# Sheet1.net
KiCad netlist of a schematic drawn in Altium Designer
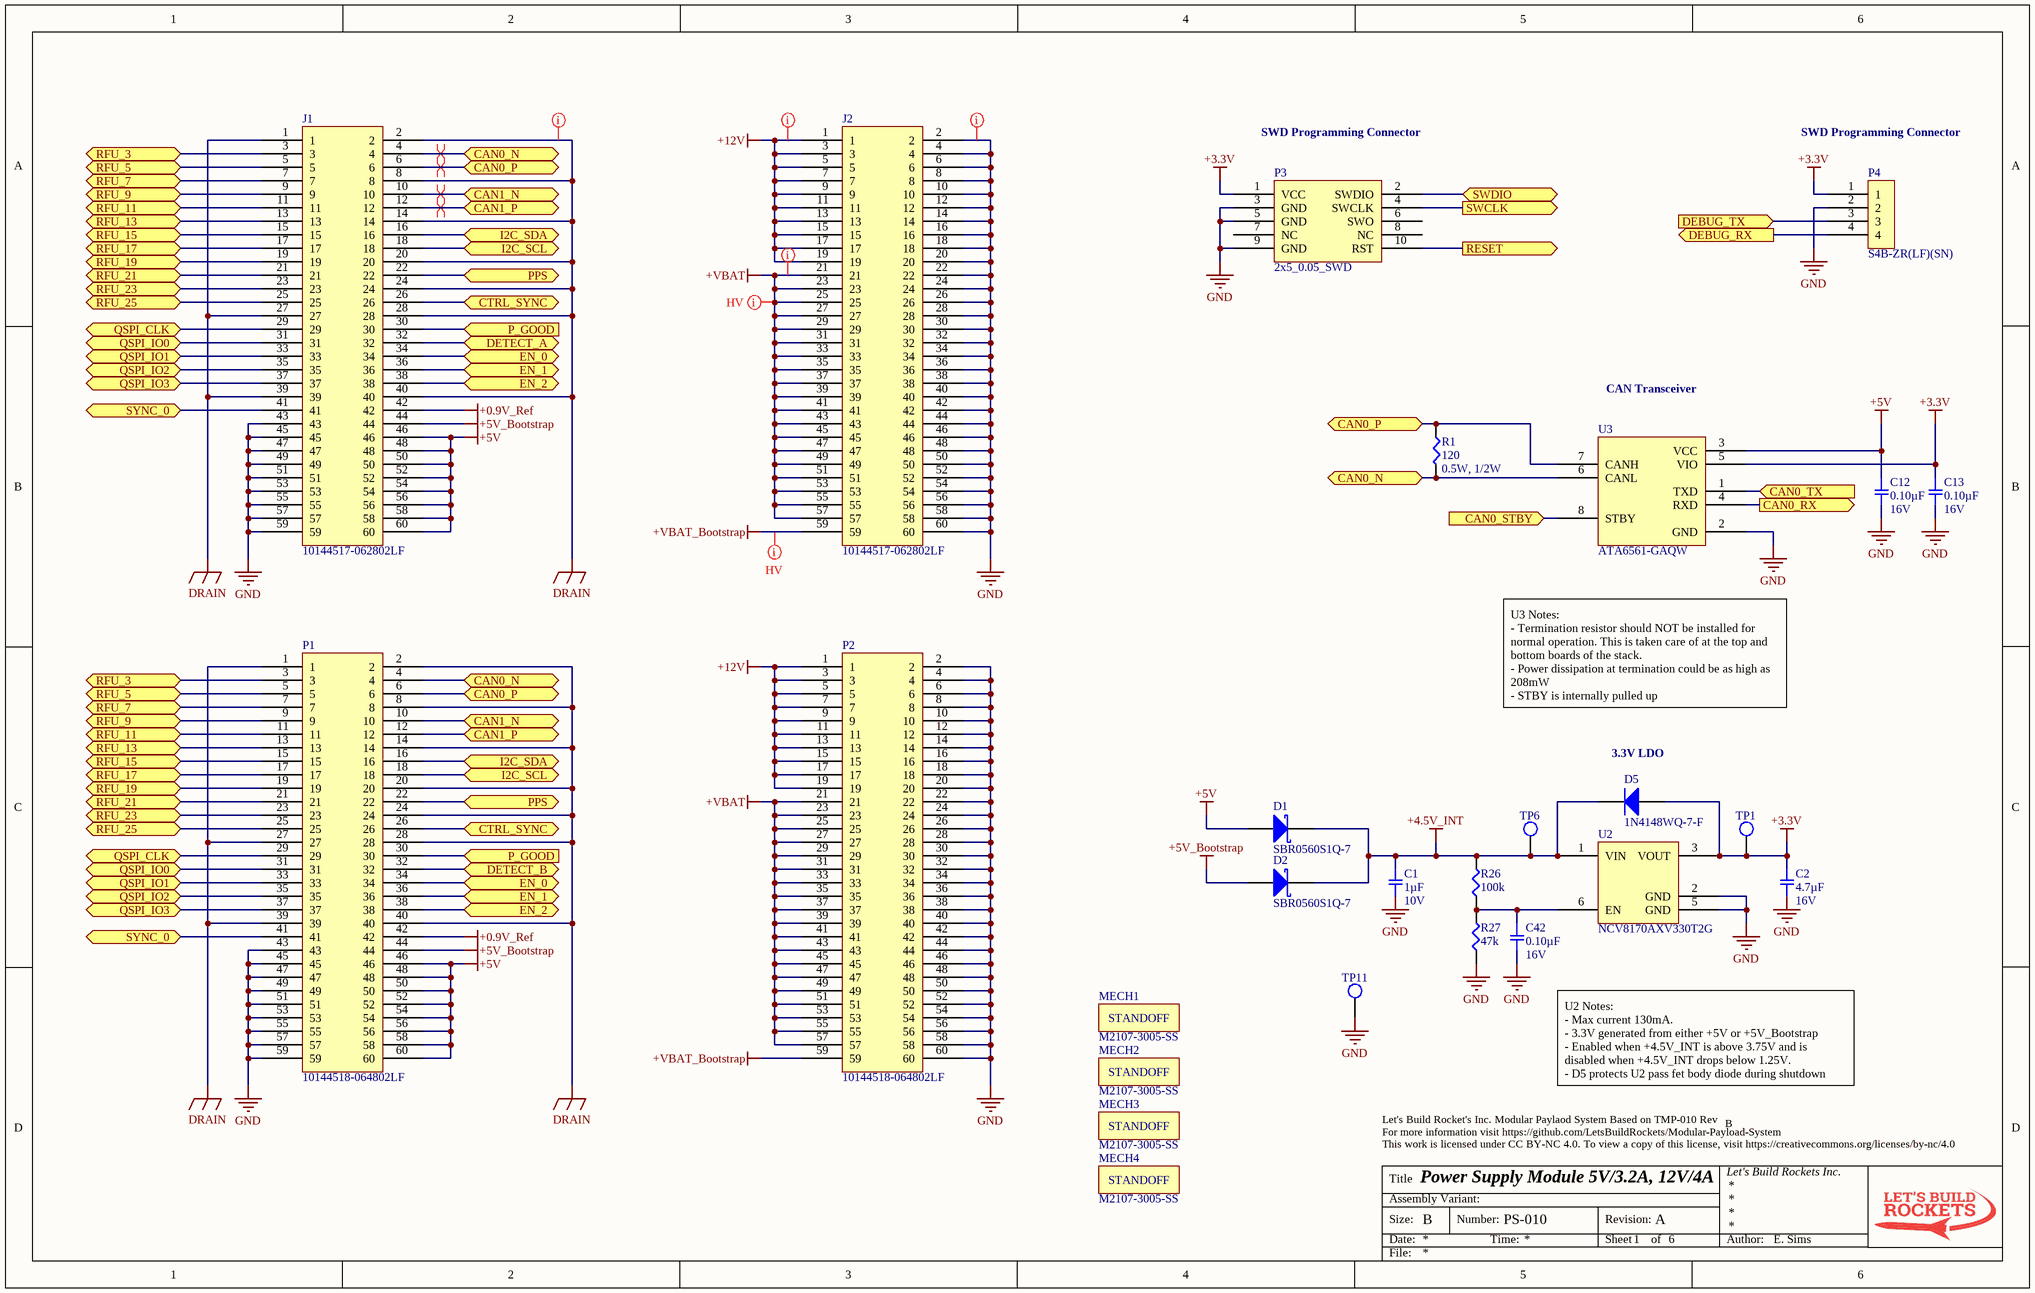
[diagram p0: Sheet1.SchDoc]

(export (version "E")
  (design (tool "Eeschema 10.0.6"))
  (components
    (comp (ref "C1")
      (value "1µF")
      (footprint "SMD-0402C")
      (description "CAP CER 1UF 10V X7S 0402")
      (fields
        (field (name "DIGI-KEY PART NUMBER") "490-13409-1-ND")
        (field (name "PART NUMBER") "GCM155C71A105KE38D")
        (field (name "VOLTAGE") "10V")
      )
      (libsource (lib "capacitor_murata_0402") (part "GCM155C71A105KE38D"))
    )
    (comp (ref "C2")
      (value "4.7µF")
      (footprint "SMD-0805C")
      (description "CAP CER 4.7UF 16V X7R 0805")
      (fields
        (field (name "DIGI-KEY PART NUMBER") "490-10557-1-ND")
        (field (name "PART NUMBER") "GCJ21BR71C475KA01L")
        (field (name "VOLTAGE") "16V")
      )
      (libsource (lib "capacitor_murata_0805") (part "GCJ21BR71C475KA01L"))
    )
    (comp (ref "C12")
      (value "0.10µF")
      (footprint "SMD-0402C")
      (description "CAP CER 0.1UF 16V X7R 0402")
      (fields
        (field (name "DIGI-KEY PART NUMBER") "490-4759-1-ND")
        (field (name "PART NUMBER") "GCM155R71C104KA55D")
        (field (name "VOLTAGE") "16V")
      )
      (libsource (lib "capacitor_murata_0402") (part "GCM155R71C104KA55D"))
    )
    (comp (ref "C13")
      (value "0.10µF")
      (footprint "SMD-0402C")
      (description "CAP CER 0.1UF 16V X7R 0402")
      (fields
        (field (name "DIGI-KEY PART NUMBER") "490-4759-1-ND")
        (field (name "PART NUMBER") "GCM155R71C104KA55D")
        (field (name "VOLTAGE") "16V")
      )
      (libsource (lib "capacitor_murata_0402") (part "GCM155R71C104KA55D"))
    )
    (comp (ref "C42")
      (value "0.10µF")
      (footprint "SMD-0402C")
      (description "CAP CER 0.1UF 16V X7R 0402")
      (fields
        (field (name "DIGI-KEY PART NUMBER") "490-4759-1-ND")
        (field (name "PART NUMBER") "GCM155R71C104KA55D")
        (field (name "VOLTAGE") "16V")
      )
      (libsource (lib "capacitor_murata_0402") (part "GCM155R71C104KA55D"))
    )
    (comp (ref "D1")
      (value "SBR0560S1Q-7")
      (footprint "SOD123")
      (libsource (lib "ModularPayload") (part "SBR0560S1Q-7"))
    )
    (comp (ref "D2")
      (value "SBR0560S1Q-7")
      (footprint "SOD123")
      (libsource (lib "ModularPayload") (part "SBR0560S1Q-7"))
    )
    (comp (ref "D5")
      (value "1N4148WQ-7-F")
      (footprint "SOD123")
      (libsource (lib "ModularPayload") (part "1N4148WQ-7-F"))
    )
    (comp (ref "J1")
      (value "10144517-062802LF")
      (footprint "10144517-062802LF")
      (libsource (lib "ModularPayload") (part "10144517-062802LF"))
    )
    (comp (ref "J2")
      (value "10144517-062802LF")
      (footprint "10144517-062802LF")
      (libsource (lib "ModularPayload") (part "10144517-062802LF"))
    )
    (comp (ref "MECH1")
      (value "M2107-3005-SS")
      (footprint "M2107-3005-SS")
      (libsource (lib "ModularPayload") (part "M2107-3005-SS"))
    )
    (comp (ref "MECH2")
      (value "M2107-3005-SS")
      (footprint "M2107-3005-SS")
      (libsource (lib "ModularPayload") (part "M2107-3005-SS"))
    )
    (comp (ref "MECH3")
      (value "M2107-3005-SS")
      (footprint "M2107-3005-SS")
      (libsource (lib "ModularPayload") (part "M2107-3005-SS"))
    )
    (comp (ref "MECH4")
      (value "M2107-3005-SS")
      (footprint "M2107-3005-SS")
      (libsource (lib "ModularPayload") (part "M2107-3005-SS"))
    )
    (comp (ref "P1")
      (value "10144518-064802LF")
      (footprint "10144518-064802LF")
      (libsource (lib "ModularPayload") (part "10144518-064802LF"))
    )
    (comp (ref "P2")
      (value "10144518-064802LF")
      (footprint "10144518-064802LF")
      (libsource (lib "ModularPayload") (part "10144518-064802LF"))
    )
    (comp (ref "P3")
      (value "2x5_0.05_SWD")
      (footprint "2x5_0.05_R")
      (libsource (lib "ModularPayload") (part "2x5_0.05_SWD"))
    )
    (comp (ref "P4")
      (value "S4B-ZR(LF)(SN)")
      (footprint "S4B-ZR(LF)(SN)")
      (libsource (lib "ModularPayload") (part "S4B-ZR(LF)(SN)"))
    )
    (comp (ref "R1")
      (value "120")
      (footprint "SMD-0805-RES")
      (description "RES SMD 120 OHM 5% 1/2W 0805")
      (fields
        (field (name "PART NUMBER") "ERJ-P6WJ121V")
        (field (name "DIGI-KEY PART NUMBER") "P16943CT-ND")
        (field (name "POWER (WATTS)") "0.5W, 1/2W")
      )
      (libsource (lib "Panasonic_ERJ_0805") (part "ERJ-P6WJ121V"))
    )
    (comp (ref "R26")
      (value "100k")
      (footprint "SMD-0402-RES")
      (description "RES SMD 100K OHM 5% 1/10W 0402")
      (fields (field (name "PART NUMBER") "ERJ-2GEJ104X") (field (name "DIGI-KEY PART NUMBER") "P100KJCT-ND"))
      (libsource (lib "Panasonic_ERJ_0402") (part "ERJ-2GEJ104X"))
    )
    (comp (ref "R27")
      (value "47k")
      (footprint "SMD-0402-RES")
      (description "RES SMD 47K OHM 5% 1/10W 0402")
      (fields (field (name "PART NUMBER") "ERJ-2GEJ473X") (field (name "DIGI-KEY PART NUMBER") "P47KJCT-ND"))
      (libsource (lib "Panasonic_ERJ_0402") (part "ERJ-2GEJ473X"))
    )
    (comp (ref "TP1") (value "TP") (footprint "TP_SMD_40") (libsource (lib "TP") (part "TP")))
    (comp (ref "TP6") (value "TP") (footprint "TP_SMD_40") (libsource (lib "TP") (part "TP")))
    (comp (ref "TP11") (value "TP") (footprint "TP_SMD_40") (libsource (lib "TP") (part "TP")))
    (comp (ref "U2")
      (value "NCV8170AXV330T2G")
      (footprint "SOTFL50P160X60-6N")
      (libsource (lib "ModularPayload") (part "NCV8170AXV330T2G"))
    )
    (comp (ref "U3")
      (value "ATA6561-GAQW")
      (footprint "SOIC127P600X175-8N")
      (libsource (lib "ModularPayload") (part "ATA6561-GAQW"))
    )
  )
  (nets
    (net (code "1") (name "+0.9V_Ref") (class "Default")
      (node (ref "J1") (pin "42") (pinfunction "42_42") (pintype "passive"))
      (node (ref "P1") (pin "42") (pinfunction "42_42") (pintype "passive"))
    )
    (net (code "2") (name "+3.3V") (class "Default")
      (node (ref "C13") (pin "1") (pinfunction "1_1") (pintype "passive"))
      (node (ref "C2") (pin "2") (pinfunction "2_2") (pintype "passive"))
      (node (ref "D5") (pin "A") (pinfunction "A_A") (pintype "passive"))
      (node (ref "P3") (pin "1") (pinfunction "VCC_1") (pintype "passive"))
      (node (ref "P4") (pin "1") (pinfunction "1_1") (pintype "passive"))
      (node (ref "TP1") (pin "1") (pintype "passive"))
      (node (ref "U2") (pin "3") (pinfunction "VOUT_3") (pintype "passive"))
      (node (ref "U3") (pin "5") (pinfunction "VIO_5") (pintype "passive"))
    )
    (net (code "3") (name "+4.5V_INT") (class "Default")
      (node (ref "C1") (pin "2") (pinfunction "2_2") (pintype "passive"))
      (node (ref "D1") (pin "K") (pinfunction "K_K") (pintype "passive"))
      (node (ref "D2") (pin "K") (pinfunction "K_K") (pintype "passive"))
      (node (ref "D5") (pin "K") (pinfunction "K_K") (pintype "passive"))
      (node (ref "R26") (pin "2") (pinfunction "2_2") (pintype "passive"))
      (node (ref "TP6") (pin "1") (pintype "passive"))
      (node (ref "U2") (pin "1") (pinfunction "VIN_1") (pintype "passive"))
    )
    (net (code "4") (name "+5V") (class "Default")
      (node (ref "C12") (pin "1") (pinfunction "1_1") (pintype "passive"))
      (node (ref "D1") (pin "A") (pinfunction "A_A") (pintype "passive"))
      (node (ref "J1") (pin "46") (pinfunction "46_46") (pintype "passive"))
      (node (ref "J1") (pin "48") (pinfunction "48_48") (pintype "passive"))
      (node (ref "J1") (pin "50") (pinfunction "50_50") (pintype "passive"))
      (node (ref "J1") (pin "52") (pinfunction "52_52") (pintype "passive"))
      (node (ref "J1") (pin "54") (pinfunction "54_54") (pintype "passive"))
      (node (ref "J1") (pin "56") (pinfunction "56_56") (pintype "passive"))
      (node (ref "J1") (pin "58") (pinfunction "58_58") (pintype "passive"))
      (node (ref "J1") (pin "60") (pinfunction "60_60") (pintype "passive"))
      (node (ref "P1") (pin "46") (pinfunction "46_46") (pintype "passive"))
      (node (ref "P1") (pin "48") (pinfunction "48_48") (pintype "passive"))
      (node (ref "P1") (pin "50") (pinfunction "50_50") (pintype "passive"))
      (node (ref "P1") (pin "52") (pinfunction "52_52") (pintype "passive"))
      (node (ref "P1") (pin "54") (pinfunction "54_54") (pintype "passive"))
      (node (ref "P1") (pin "56") (pinfunction "56_56") (pintype "passive"))
      (node (ref "P1") (pin "58") (pinfunction "58_58") (pintype "passive"))
      (node (ref "P1") (pin "60") (pinfunction "60_60") (pintype "passive"))
      (node (ref "U3") (pin "3") (pinfunction "VCC_3") (pintype "passive"))
    )
    (net (code "5") (name "+5V_Bootstrap") (class "Default")
      (node (ref "D2") (pin "A") (pinfunction "A_A") (pintype "passive"))
      (node (ref "J1") (pin "44") (pinfunction "44_44") (pintype "passive"))
      (node (ref "P1") (pin "44") (pinfunction "44_44") (pintype "passive"))
    )
    (net (code "6") (name "+12V") (class "Default")
      (node (ref "J2") (pin "1") (pinfunction "1_1") (pintype "passive"))
      (node (ref "J2") (pin "11") (pinfunction "11_11") (pintype "passive"))
      (node (ref "J2") (pin "13") (pinfunction "13_13") (pintype "passive"))
      (node (ref "J2") (pin "15") (pinfunction "15_15") (pintype "passive"))
      (node (ref "J2") (pin "17") (pinfunction "17_17") (pintype "passive"))
      (node (ref "J2") (pin "19") (pinfunction "19_19") (pintype "passive"))
      (node (ref "J2") (pin "3") (pinfunction "3_3") (pintype "passive"))
      (node (ref "J2") (pin "5") (pinfunction "5_5") (pintype "passive"))
      (node (ref "J2") (pin "7") (pinfunction "7_7") (pintype "passive"))
      (node (ref "J2") (pin "9") (pinfunction "9_9") (pintype "passive"))
      (node (ref "P2") (pin "1") (pinfunction "1_1") (pintype "passive"))
      (node (ref "P2") (pin "11") (pinfunction "11_11") (pintype "passive"))
      (node (ref "P2") (pin "13") (pinfunction "13_13") (pintype "passive"))
      (node (ref "P2") (pin "15") (pinfunction "15_15") (pintype "passive"))
      (node (ref "P2") (pin "17") (pinfunction "17_17") (pintype "passive"))
      (node (ref "P2") (pin "19") (pinfunction "19_19") (pintype "passive"))
      (node (ref "P2") (pin "3") (pinfunction "3_3") (pintype "passive"))
      (node (ref "P2") (pin "5") (pinfunction "5_5") (pintype "passive"))
      (node (ref "P2") (pin "7") (pinfunction "7_7") (pintype "passive"))
      (node (ref "P2") (pin "9") (pinfunction "9_9") (pintype "passive"))
    )
    (net (code "7") (name "+VBAT") (class "Default")
      (node (ref "J2") (pin "21") (pinfunction "21_21") (pintype "passive"))
      (node (ref "J2") (pin "23") (pinfunction "23_23") (pintype "passive"))
      (node (ref "J2") (pin "25") (pinfunction "25_25") (pintype "passive"))
      (node (ref "J2") (pin "27") (pinfunction "27_27") (pintype "passive"))
      (node (ref "J2") (pin "29") (pinfunction "29_29") (pintype "passive"))
      (node (ref "J2") (pin "31") (pinfunction "31_31") (pintype "passive"))
      (node (ref "J2") (pin "33") (pinfunction "33_33") (pintype "passive"))
      (node (ref "J2") (pin "35") (pinfunction "35_35") (pintype "passive"))
      (node (ref "J2") (pin "37") (pinfunction "37_37") (pintype "passive"))
      (node (ref "J2") (pin "39") (pinfunction "39_39") (pintype "passive"))
      (node (ref "J2") (pin "41") (pinfunction "41_41") (pintype "passive"))
      (node (ref "J2") (pin "43") (pinfunction "43_43") (pintype "passive"))
      (node (ref "J2") (pin "45") (pinfunction "45_45") (pintype "passive"))
      (node (ref "J2") (pin "47") (pinfunction "47_47") (pintype "passive"))
      (node (ref "J2") (pin "49") (pinfunction "49_49") (pintype "passive"))
      (node (ref "J2") (pin "51") (pinfunction "51_51") (pintype "passive"))
      (node (ref "J2") (pin "53") (pinfunction "53_53") (pintype "passive"))
      (node (ref "J2") (pin "55") (pinfunction "55_55") (pintype "passive"))
      (node (ref "J2") (pin "57") (pinfunction "57_57") (pintype "passive"))
      (node (ref "P2") (pin "21") (pinfunction "21_21") (pintype "passive"))
      (node (ref "P2") (pin "23") (pinfunction "23_23") (pintype "passive"))
      (node (ref "P2") (pin "25") (pinfunction "25_25") (pintype "passive"))
      (node (ref "P2") (pin "27") (pinfunction "27_27") (pintype "passive"))
      (node (ref "P2") (pin "29") (pinfunction "29_29") (pintype "passive"))
      (node (ref "P2") (pin "31") (pinfunction "31_31") (pintype "passive"))
      (node (ref "P2") (pin "33") (pinfunction "33_33") (pintype "passive"))
      (node (ref "P2") (pin "35") (pinfunction "35_35") (pintype "passive"))
      (node (ref "P2") (pin "37") (pinfunction "37_37") (pintype "passive"))
      (node (ref "P2") (pin "39") (pinfunction "39_39") (pintype "passive"))
      (node (ref "P2") (pin "41") (pinfunction "41_41") (pintype "passive"))
      (node (ref "P2") (pin "43") (pinfunction "43_43") (pintype "passive"))
      (node (ref "P2") (pin "45") (pinfunction "45_45") (pintype "passive"))
      (node (ref "P2") (pin "47") (pinfunction "47_47") (pintype "passive"))
      (node (ref "P2") (pin "49") (pinfunction "49_49") (pintype "passive"))
      (node (ref "P2") (pin "51") (pinfunction "51_51") (pintype "passive"))
      (node (ref "P2") (pin "53") (pinfunction "53_53") (pintype "passive"))
      (node (ref "P2") (pin "55") (pinfunction "55_55") (pintype "passive"))
      (node (ref "P2") (pin "57") (pinfunction "57_57") (pintype "passive"))
    )
    (net (code "8") (name "+VBAT_Bootstrap") (class "Default")
      (node (ref "J2") (pin "59") (pinfunction "59_59") (pintype "passive"))
      (node (ref "P2") (pin "59") (pinfunction "59_59") (pintype "passive"))
    )
    (net (code "9") (name "/CAN0_N") (class "Default")
      (node (ref "J1") (pin "4") (pinfunction "4_4") (pintype "passive"))
      (node (ref "P1") (pin "4") (pinfunction "4_4") (pintype "passive"))
      (node (ref "R1") (pin "2") (pinfunction "2_2") (pintype "passive"))
      (node (ref "U3") (pin "6") (pinfunction "CANL_6") (pintype "passive"))
    )
    (net (code "10") (name "/CAN0_P") (class "Default")
      (node (ref "J1") (pin "6") (pinfunction "6_6") (pintype "passive"))
      (node (ref "P1") (pin "6") (pinfunction "6_6") (pintype "passive"))
      (node (ref "R1") (pin "1") (pinfunction "1_1") (pintype "passive"))
      (node (ref "U3") (pin "7") (pinfunction "CANH_7") (pintype "passive"))
    )
    (net (code "11") (name "/CAN0_RX") (class "Default")
      (node (ref "U3") (pin "4") (pinfunction "RXD_4") (pintype "passive"))
    )
    (net (code "12") (name "/CAN0_STBY") (class "Default")
      (node (ref "U3") (pin "8") (pinfunction "STBY_8") (pintype "passive"))
    )
    (net (code "13") (name "/CAN0_TX") (class "Default")
      (node (ref "U3") (pin "1") (pinfunction "TXD_1") (pintype "passive"))
    )
    (net (code "14") (name "/CAN1_N") (class "Default")
      (node (ref "J1") (pin "10") (pinfunction "10_10") (pintype "passive"))
      (node (ref "P1") (pin "10") (pinfunction "10_10") (pintype "passive"))
    )
    (net (code "15") (name "/CAN1_P") (class "Default")
      (node (ref "J1") (pin "12") (pinfunction "12_12") (pintype "passive"))
      (node (ref "P1") (pin "12") (pinfunction "12_12") (pintype "passive"))
    )
    (net (code "16") (name "/CTRL_SYNC") (class "Default")
      (node (ref "J1") (pin "26") (pinfunction "26_26") (pintype "passive"))
      (node (ref "P1") (pin "26") (pinfunction "26_26") (pintype "passive"))
    )
    (net (code "17") (name "/DEBUG_RX") (class "Default")
      (node (ref "P4") (pin "4") (pinfunction "4_4") (pintype "passive"))
    )
    (net (code "18") (name "/DEBUG_TX") (class "Default")
      (node (ref "P4") (pin "3") (pinfunction "3_3") (pintype "passive"))
    )
    (net (code "19") (name "/DETECT_A") (class "Default")
      (node (ref "J1") (pin "32") (pinfunction "32_32") (pintype "passive"))
    )
    (net (code "20") (name "/DETECT_B") (class "Default")
      (node (ref "P1") (pin "32") (pinfunction "32_32") (pintype "passive"))
    )
    (net (code "21") (name "/EN_0") (class "Default")
      (node (ref "J1") (pin "34") (pinfunction "34_34") (pintype "passive"))
      (node (ref "P1") (pin "34") (pinfunction "34_34") (pintype "passive"))
    )
    (net (code "22") (name "/EN_1") (class "Default")
      (node (ref "J1") (pin "36") (pinfunction "36_36") (pintype "passive"))
      (node (ref "P1") (pin "36") (pinfunction "36_36") (pintype "passive"))
    )
    (net (code "23") (name "/EN_2") (class "Default")
      (node (ref "J1") (pin "38") (pinfunction "38_38") (pintype "passive"))
      (node (ref "P1") (pin "38") (pinfunction "38_38") (pintype "passive"))
    )
    (net (code "24") (name "/I2C_SCL") (class "Default")
      (node (ref "J1") (pin "18") (pinfunction "18_18") (pintype "passive"))
      (node (ref "P1") (pin "18") (pinfunction "18_18") (pintype "passive"))
    )
    (net (code "25") (name "/I2C_SDA") (class "Default")
      (node (ref "J1") (pin "16") (pinfunction "16_16") (pintype "passive"))
      (node (ref "P1") (pin "16") (pinfunction "16_16") (pintype "passive"))
    )
    (net (code "26") (name "/PPS") (class "Default")
      (node (ref "J1") (pin "22") (pinfunction "22_22") (pintype "passive"))
      (node (ref "P1") (pin "22") (pinfunction "22_22") (pintype "passive"))
    )
    (net (code "27") (name "/P_GOOD") (class "Default")
      (node (ref "J1") (pin "30") (pinfunction "30_30") (pintype "passive"))
      (node (ref "P1") (pin "30") (pinfunction "30_30") (pintype "passive"))
    )
    (net (code "28") (name "/QSPI_CLK") (class "Default")
      (node (ref "J1") (pin "29") (pinfunction "29_29") (pintype "passive"))
      (node (ref "P1") (pin "29") (pinfunction "29_29") (pintype "passive"))
    )
    (net (code "29") (name "/QSPI_IO0") (class "Default")
      (node (ref "J1") (pin "31") (pinfunction "31_31") (pintype "passive"))
      (node (ref "P1") (pin "31") (pinfunction "31_31") (pintype "passive"))
    )
    (net (code "30") (name "/QSPI_IO1") (class "Default")
      (node (ref "J1") (pin "33") (pinfunction "33_33") (pintype "passive"))
      (node (ref "P1") (pin "33") (pinfunction "33_33") (pintype "passive"))
    )
    (net (code "31") (name "/QSPI_IO2") (class "Default")
      (node (ref "J1") (pin "35") (pinfunction "35_35") (pintype "passive"))
      (node (ref "P1") (pin "35") (pinfunction "35_35") (pintype "passive"))
    )
    (net (code "32") (name "/QSPI_IO3") (class "Default")
      (node (ref "J1") (pin "37") (pinfunction "37_37") (pintype "passive"))
      (node (ref "P1") (pin "37") (pinfunction "37_37") (pintype "passive"))
    )
    (net (code "33") (name "/RESET") (class "Default")
      (node (ref "P3") (pin "10") (pinfunction "RST_10") (pintype "passive"))
    )
    (net (code "34") (name "/RFU_3") (class "Default")
      (node (ref "J1") (pin "3") (pinfunction "3_3") (pintype "passive"))
      (node (ref "P1") (pin "3") (pinfunction "3_3") (pintype "passive"))
    )
    (net (code "35") (name "/RFU_5") (class "Default")
      (node (ref "J1") (pin "5") (pinfunction "5_5") (pintype "passive"))
      (node (ref "P1") (pin "5") (pinfunction "5_5") (pintype "passive"))
    )
    (net (code "36") (name "/RFU_7") (class "Default")
      (node (ref "J1") (pin "7") (pinfunction "7_7") (pintype "passive"))
      (node (ref "P1") (pin "7") (pinfunction "7_7") (pintype "passive"))
    )
    (net (code "37") (name "/RFU_9") (class "Default")
      (node (ref "J1") (pin "9") (pinfunction "9_9") (pintype "passive"))
      (node (ref "P1") (pin "9") (pinfunction "9_9") (pintype "passive"))
    )
    (net (code "38") (name "/RFU_11") (class "Default")
      (node (ref "J1") (pin "11") (pinfunction "11_11") (pintype "passive"))
      (node (ref "P1") (pin "11") (pinfunction "11_11") (pintype "passive"))
    )
    (net (code "39") (name "/RFU_13") (class "Default")
      (node (ref "J1") (pin "13") (pinfunction "13_13") (pintype "passive"))
      (node (ref "P1") (pin "13") (pinfunction "13_13") (pintype "passive"))
    )
    (net (code "40") (name "/RFU_15") (class "Default")
      (node (ref "J1") (pin "15") (pinfunction "15_15") (pintype "passive"))
      (node (ref "P1") (pin "15") (pinfunction "15_15") (pintype "passive"))
    )
    (net (code "41") (name "/RFU_17") (class "Default")
      (node (ref "J1") (pin "17") (pinfunction "17_17") (pintype "passive"))
      (node (ref "P1") (pin "17") (pinfunction "17_17") (pintype "passive"))
    )
    (net (code "42") (name "/RFU_19") (class "Default")
      (node (ref "J1") (pin "19") (pinfunction "19_19") (pintype "passive"))
      (node (ref "P1") (pin "19") (pinfunction "19_19") (pintype "passive"))
    )
    (net (code "43") (name "/RFU_21") (class "Default")
      (node (ref "J1") (pin "21") (pinfunction "21_21") (pintype "passive"))
      (node (ref "P1") (pin "21") (pinfunction "21_21") (pintype "passive"))
    )
    (net (code "44") (name "/RFU_23") (class "Default")
      (node (ref "J1") (pin "23") (pinfunction "23_23") (pintype "passive"))
      (node (ref "P1") (pin "23") (pinfunction "23_23") (pintype "passive"))
    )
    (net (code "45") (name "/RFU_25") (class "Default")
      (node (ref "J1") (pin "25") (pinfunction "25_25") (pintype "passive"))
      (node (ref "P1") (pin "25") (pinfunction "25_25") (pintype "passive"))
    )
    (net (code "46") (name "/SWCLK") (class "Default")
      (node (ref "P3") (pin "4") (pinfunction "SWCLK_4") (pintype "passive"))
    )
    (net (code "47") (name "/SWDIO") (class "Default")
      (node (ref "P3") (pin "2") (pinfunction "SWDIO_2") (pintype "passive"))
    )
    (net (code "48") (name "/SYNC_0") (class "Default")
      (node (ref "J1") (pin "41") (pinfunction "41_41") (pintype "passive"))
      (node (ref "P1") (pin "41") (pinfunction "41_41") (pintype "passive"))
    )
    (net (code "49") (name "DRAIN") (class "Default")
      (node (ref "J1") (pin "1") (pinfunction "1_1") (pintype "passive"))
      (node (ref "J1") (pin "14") (pinfunction "14_14") (pintype "passive"))
      (node (ref "J1") (pin "2") (pinfunction "2_2") (pintype "passive"))
      (node (ref "J1") (pin "20") (pinfunction "20_20") (pintype "passive"))
      (node (ref "J1") (pin "24") (pinfunction "24_24") (pintype "passive"))
      (node (ref "J1") (pin "27") (pinfunction "27_27") (pintype "passive"))
      (node (ref "J1") (pin "28") (pinfunction "28_28") (pintype "passive"))
      (node (ref "J1") (pin "39") (pinfunction "39_39") (pintype "passive"))
      (node (ref "J1") (pin "40") (pinfunction "40_40") (pintype "passive"))
      (node (ref "J1") (pin "8") (pinfunction "8_8") (pintype "passive"))
      (node (ref "P1") (pin "1") (pinfunction "1_1") (pintype "passive"))
      (node (ref "P1") (pin "14") (pinfunction "14_14") (pintype "passive"))
      (node (ref "P1") (pin "2") (pinfunction "2_2") (pintype "passive"))
      (node (ref "P1") (pin "20") (pinfunction "20_20") (pintype "passive"))
      (node (ref "P1") (pin "24") (pinfunction "24_24") (pintype "passive"))
      (node (ref "P1") (pin "27") (pinfunction "27_27") (pintype "passive"))
      (node (ref "P1") (pin "28") (pinfunction "28_28") (pintype "passive"))
      (node (ref "P1") (pin "39") (pinfunction "39_39") (pintype "passive"))
      (node (ref "P1") (pin "40") (pinfunction "40_40") (pintype "passive"))
      (node (ref "P1") (pin "8") (pinfunction "8_8") (pintype "passive"))
    )
    (net (code "50") (name "GND") (class "Default")
      (node (ref "C1") (pin "1") (pinfunction "1_1") (pintype "passive"))
      (node (ref "C12") (pin "2") (pinfunction "2_2") (pintype "passive"))
      (node (ref "C13") (pin "2") (pinfunction "2_2") (pintype "passive"))
      (node (ref "C2") (pin "1") (pinfunction "1_1") (pintype "passive"))
      (node (ref "C42") (pin "2") (pinfunction "2_2") (pintype "passive"))
      (node (ref "J1") (pin "43") (pinfunction "43_43") (pintype "passive"))
      (node (ref "J1") (pin "45") (pinfunction "45_45") (pintype "passive"))
      (node (ref "J1") (pin "47") (pinfunction "47_47") (pintype "passive"))
      (node (ref "J1") (pin "49") (pinfunction "49_49") (pintype "passive"))
      (node (ref "J1") (pin "51") (pinfunction "51_51") (pintype "passive"))
      (node (ref "J1") (pin "53") (pinfunction "53_53") (pintype "passive"))
      (node (ref "J1") (pin "55") (pinfunction "55_55") (pintype "passive"))
      (node (ref "J1") (pin "57") (pinfunction "57_57") (pintype "passive"))
      (node (ref "J1") (pin "59") (pinfunction "59_59") (pintype "passive"))
      (node (ref "J2") (pin "10") (pinfunction "10_10") (pintype "passive"))
      (node (ref "J2") (pin "12") (pinfunction "12_12") (pintype "passive"))
      (node (ref "J2") (pin "14") (pinfunction "14_14") (pintype "passive"))
      (node (ref "J2") (pin "16") (pinfunction "16_16") (pintype "passive"))
      (node (ref "J2") (pin "18") (pinfunction "18_18") (pintype "passive"))
      (node (ref "J2") (pin "2") (pinfunction "2_2") (pintype "passive"))
      (node (ref "J2") (pin "20") (pinfunction "20_20") (pintype "passive"))
      (node (ref "J2") (pin "22") (pinfunction "22_22") (pintype "passive"))
      (node (ref "J2") (pin "24") (pinfunction "24_24") (pintype "passive"))
      (node (ref "J2") (pin "26") (pinfunction "26_26") (pintype "passive"))
      (node (ref "J2") (pin "28") (pinfunction "28_28") (pintype "passive"))
      (node (ref "J2") (pin "30") (pinfunction "30_30") (pintype "passive"))
      (node (ref "J2") (pin "32") (pinfunction "32_32") (pintype "passive"))
      (node (ref "J2") (pin "34") (pinfunction "34_34") (pintype "passive"))
      (node (ref "J2") (pin "36") (pinfunction "36_36") (pintype "passive"))
      (node (ref "J2") (pin "38") (pinfunction "38_38") (pintype "passive"))
      (node (ref "J2") (pin "4") (pinfunction "4_4") (pintype "passive"))
      (node (ref "J2") (pin "40") (pinfunction "40_40") (pintype "passive"))
      (node (ref "J2") (pin "42") (pinfunction "42_42") (pintype "passive"))
      (node (ref "J2") (pin "44") (pinfunction "44_44") (pintype "passive"))
      (node (ref "J2") (pin "46") (pinfunction "46_46") (pintype "passive"))
      (node (ref "J2") (pin "48") (pinfunction "48_48") (pintype "passive"))
      (node (ref "J2") (pin "50") (pinfunction "50_50") (pintype "passive"))
      (node (ref "J2") (pin "52") (pinfunction "52_52") (pintype "passive"))
      (node (ref "J2") (pin "54") (pinfunction "54_54") (pintype "passive"))
      (node (ref "J2") (pin "56") (pinfunction "56_56") (pintype "passive"))
      (node (ref "J2") (pin "58") (pinfunction "58_58") (pintype "passive"))
      (node (ref "J2") (pin "6") (pinfunction "6_6") (pintype "passive"))
      (node (ref "J2") (pin "60") (pinfunction "60_60") (pintype "passive"))
      (node (ref "J2") (pin "8") (pinfunction "8_8") (pintype "passive"))
      (node (ref "P1") (pin "43") (pinfunction "43_43") (pintype "passive"))
      (node (ref "P1") (pin "45") (pinfunction "45_45") (pintype "passive"))
      (node (ref "P1") (pin "47") (pinfunction "47_47") (pintype "passive"))
      (node (ref "P1") (pin "49") (pinfunction "49_49") (pintype "passive"))
      (node (ref "P1") (pin "51") (pinfunction "51_51") (pintype "passive"))
      (node (ref "P1") (pin "53") (pinfunction "53_53") (pintype "passive"))
      (node (ref "P1") (pin "55") (pinfunction "55_55") (pintype "passive"))
      (node (ref "P1") (pin "57") (pinfunction "57_57") (pintype "passive"))
      (node (ref "P1") (pin "59") (pinfunction "59_59") (pintype "passive"))
      (node (ref "P2") (pin "10") (pinfunction "10_10") (pintype "passive"))
      (node (ref "P2") (pin "12") (pinfunction "12_12") (pintype "passive"))
      (node (ref "P2") (pin "14") (pinfunction "14_14") (pintype "passive"))
      (node (ref "P2") (pin "16") (pinfunction "16_16") (pintype "passive"))
      (node (ref "P2") (pin "18") (pinfunction "18_18") (pintype "passive"))
      (node (ref "P2") (pin "2") (pinfunction "2_2") (pintype "passive"))
      (node (ref "P2") (pin "20") (pinfunction "20_20") (pintype "passive"))
      (node (ref "P2") (pin "22") (pinfunction "22_22") (pintype "passive"))
      (node (ref "P2") (pin "24") (pinfunction "24_24") (pintype "passive"))
      (node (ref "P2") (pin "26") (pinfunction "26_26") (pintype "passive"))
      (node (ref "P2") (pin "28") (pinfunction "28_28") (pintype "passive"))
      (node (ref "P2") (pin "30") (pinfunction "30_30") (pintype "passive"))
      (node (ref "P2") (pin "32") (pinfunction "32_32") (pintype "passive"))
      (node (ref "P2") (pin "34") (pinfunction "34_34") (pintype "passive"))
      (node (ref "P2") (pin "36") (pinfunction "36_36") (pintype "passive"))
      (node (ref "P2") (pin "38") (pinfunction "38_38") (pintype "passive"))
      (node (ref "P2") (pin "4") (pinfunction "4_4") (pintype "passive"))
      (node (ref "P2") (pin "40") (pinfunction "40_40") (pintype "passive"))
      (node (ref "P2") (pin "42") (pinfunction "42_42") (pintype "passive"))
      (node (ref "P2") (pin "44") (pinfunction "44_44") (pintype "passive"))
      (node (ref "P2") (pin "46") (pinfunction "46_46") (pintype "passive"))
      (node (ref "P2") (pin "48") (pinfunction "48_48") (pintype "passive"))
      (node (ref "P2") (pin "50") (pinfunction "50_50") (pintype "passive"))
      (node (ref "P2") (pin "52") (pinfunction "52_52") (pintype "passive"))
      (node (ref "P2") (pin "54") (pinfunction "54_54") (pintype "passive"))
      (node (ref "P2") (pin "56") (pinfunction "56_56") (pintype "passive"))
      (node (ref "P2") (pin "58") (pinfunction "58_58") (pintype "passive"))
      (node (ref "P2") (pin "6") (pinfunction "6_6") (pintype "passive"))
      (node (ref "P2") (pin "60") (pinfunction "60_60") (pintype "passive"))
      (node (ref "P2") (pin "8") (pinfunction "8_8") (pintype "passive"))
      (node (ref "P3") (pin "3") (pinfunction "GND_3") (pintype "passive"))
      (node (ref "P3") (pin "5") (pinfunction "GND_5") (pintype "passive"))
      (node (ref "P3") (pin "9") (pinfunction "GND_9") (pintype "passive"))
      (node (ref "P4") (pin "2") (pinfunction "2_2") (pintype "passive"))
      (node (ref "R27") (pin "1") (pinfunction "1_1") (pintype "passive"))
      (node (ref "TP11") (pin "1") (pintype "passive"))
      (node (ref "U2") (pin "2") (pinfunction "GND_2") (pintype "passive"))
      (node (ref "U2") (pin "5") (pinfunction "GND_5") (pintype "passive"))
      (node (ref "U3") (pin "2") (pinfunction "GND_2") (pintype "passive"))
    )
    (net (code "51") (name "Net-(U2-EN)") (class "Default")
      (node (ref "C42") (pin "1") (pinfunction "1_1") (pintype "passive"))
      (node (ref "R26") (pin "1") (pinfunction "1_1") (pintype "passive"))
      (node (ref "R27") (pin "2") (pinfunction "2_2") (pintype "passive"))
      (node (ref "U2") (pin "6") (pinfunction "EN_6") (pintype "passive"))
    )
    (net (code "52") (name "unconnected-(P3-NC-Pad7)") (class "Default")
      (node (ref "P3") (pin "7") (pinfunction "NC_7") (pintype "passive"))
    )
    (net (code "53") (name "unconnected-(P3-NC-Pad8)") (class "Default")
      (node (ref "P3") (pin "8") (pinfunction "NC_8") (pintype "passive"))
    )
    (net (code "54") (name "unconnected-(P3-SWO-Pad6)") (class "Default")
      (node (ref "P3") (pin "6") (pinfunction "SWO_6") (pintype "passive"))
    )
  )
)
